# Yitran_IT900_Hutschiene_PIM7A_1_1.net
KiCad netlist of a schematic drawn in EAGLE
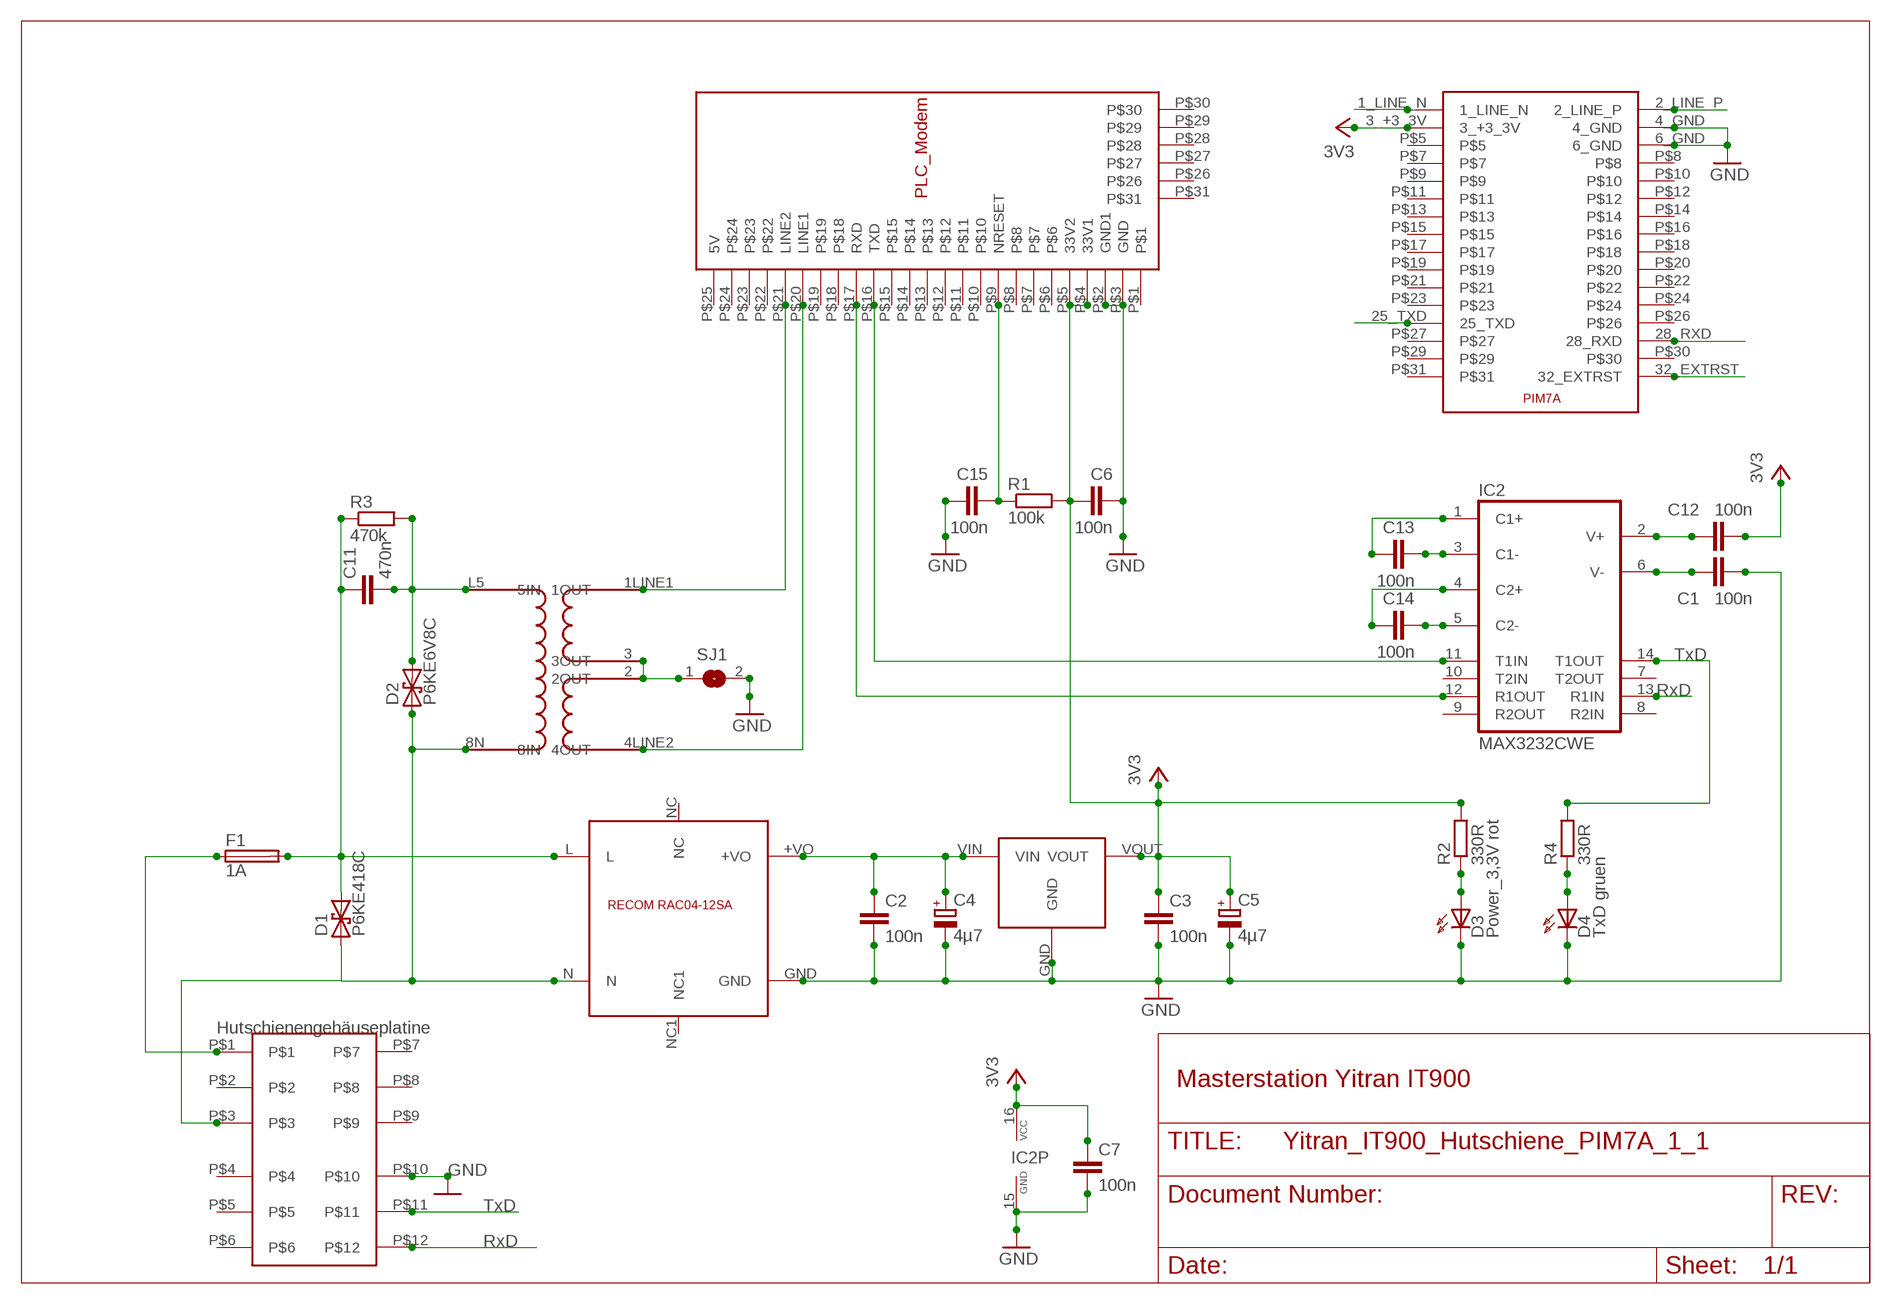
[diagram p0: schematic, sheet 1]

(export (version "E")
  (design (tool "Eeschema 10.0.6"))
  (components
    (comp (ref "C1")
      (value "100n")
      (footprint "eagle-import:C1206K")
      (libsource (lib "eagle-import") (part "C-EUC1206K"))
    )
    (comp (ref "C2")
      (value "100n")
      (footprint "eagle-import:C1206K")
      (libsource (lib "eagle-import") (part "C-EUC1206K"))
    )
    (comp (ref "C3")
      (value "100n")
      (footprint "eagle-import:C1206K")
      (libsource (lib "eagle-import") (part "C-EUC1206K"))
    )
    (comp (ref "C4")
      (value "4µ7")
      (footprint "eagle-import:E2,5-5")
      (libsource (lib "eagle-import") (part "CPOL-EUE2.5-5"))
    )
    (comp (ref "C5")
      (value "4µ7")
      (footprint "eagle-import:E2,5-5")
      (libsource (lib "eagle-import") (part "CPOL-EUE2.5-5"))
    )
    (comp (ref "C6")
      (value "100n")
      (footprint "eagle-import:C1206K")
      (libsource (lib "eagle-import") (part "C-EUC1206K"))
    )
    (comp (ref "C7")
      (value "100n")
      (footprint "eagle-import:C1206K")
      (libsource (lib "eagle-import") (part "C-EUC1206K"))
    )
    (comp (ref "C11")
      (value "470n")
      (footprint "eagle-import:C150-091X182")
      (libsource (lib "eagle-import") (part "C-EU150-091X182"))
    )
    (comp (ref "C12")
      (value "100n")
      (footprint "eagle-import:C1206K")
      (libsource (lib "eagle-import") (part "C-EUC1206K"))
    )
    (comp (ref "C13")
      (value "100n")
      (footprint "eagle-import:C1206K")
      (libsource (lib "eagle-import") (part "C-EUC1206K"))
    )
    (comp (ref "C14")
      (value "100n")
      (footprint "eagle-import:C1206K")
      (libsource (lib "eagle-import") (part "C-EUC1206K"))
    )
    (comp (ref "C15")
      (value "100n")
      (footprint "eagle-import:C1206K")
      (libsource (lib "eagle-import") (part "C-EUC1206K"))
    )
    (comp (ref "D1")
      (value "P6KE418C")
      (footprint "eagle-import:CB417-15")
      (libsource (lib "eagle-import") (part "P6KEXXC"))
    )
    (comp (ref "D2")
      (value "P6KE6V8C")
      (footprint "eagle-import:CB417-15")
      (libsource (lib "eagle-import") (part "P6KEXXC"))
    )
    (comp (ref "D3")
      (value "Power_3,3V rot")
      (footprint "eagle-import:HLMP6")
      (fields (field (name "MF") "AGILENT TECHNOLOGIES") (field (name "MPN") "HLMP-6500"))
      (libsource (lib "eagle-import") (part "HLMP6"))
    )
    (comp (ref "D4")
      (value "TxD gruen")
      (footprint "eagle-import:HLMP6")
      (fields (field (name "MF") "AGILENT TECHNOLOGIES") (field (name "MPN") "HLMP-6500"))
      (libsource (lib "eagle-import") (part "HLMP6"))
    )
    (comp (ref "F1")
      (value "1A")
      (footprint "eagle-import:TR5")
      (libsource (lib "eagle-import") (part "TR5"))
    )
    (comp (ref "IC2")
      (value "MAX3232CWE")
      (footprint "eagle-import:SO16L")
      (fields (field (name "MF") "MAXIM") (field (name "MPN") "MAX3232CWE+"))
      (libsource (lib "eagle-import") (part "MAX3232WEC"))
    )
    (comp (ref "R1")
      (value "100k")
      (footprint "eagle-import:M1406")
      (libsource (lib "eagle-import") (part "R-EU_M1406"))
    )
    (comp (ref "R2")
      (value "330R")
      (footprint "eagle-import:R1206")
      (libsource (lib "eagle-import") (part "R-EU_R1206"))
    )
    (comp (ref "R3")
      (value "470k")
      (footprint "eagle-import:0309_10")
      (libsource (lib "eagle-import") (part "R-EU_0309/10"))
    )
    (comp (ref "R4")
      (value "330R")
      (footprint "eagle-import:R1206")
      (libsource (lib "eagle-import") (part "R-EU_R1206"))
    )
    (comp (ref "SJ1")
      (value "SJW")
      (footprint "eagle-import:SJW")
      (libsource (lib "eagle-import") (part "SJW"))
    )
    (comp (ref "U$1")
      (value "RECOM_783_3")
      (footprint "eagle-import:RECOM785X")
      (libsource (lib "eagle-import") (part "RECOM_785_05"))
    )
    (comp (ref "U$2")
      (value "LDG-A-12")
      (footprint "eagle-import:LDG-A-12")
      (libsource (lib "eagle-import") (part "LDG-A-12"))
    )
    (comp (ref "U$3")
      (value "MODEMSTECKER")
      (footprint "eagle-import:MODEM_FUSS")
      (libsource (lib "eagle-import") (part "MODEMSTECKER"))
    )
    (comp (ref "U$4")
      (value "IT900PIM7A")
      (footprint "eagle-import:IT900PIM7A")
      (libsource (lib "eagle-import") (part "IT900PIM7A"))
    )
    (comp (ref "U$9")
      (value "RECOM_RAC04_12SA")
      (footprint "eagle-import:RAC04_12SA")
      (libsource (lib "eagle-import") (part "RECOM_RAC04_12SA"))
    )
    (comp (ref "U$10")
      (value "PLC_UEBERTRAGER_V2")
      (footprint "eagle-import:PLC-UEBERTRAGER_V2")
      (libsource (lib "eagle-import") (part "PLC_UEBERTRAGER_V2"))
    )
  )
  (nets
    (net (code "1") (name "/EXTRST") (class "Default")
      (node (ref "C15") (pin "2") (pinfunction "2_2") (pintype "passive"))
      (node (ref "R1") (pin "1") (pinfunction "1_1") (pintype "passive"))
      (node (ref "U$3") (pin "P$9") (pinfunction "NRESET_P$9") (pintype "bidirectional"))
      (node (ref "U$4") (pin "32_EXTRST") (pinfunction "32_EXTRST_32_EXTRST") (pintype "bidirectional"))
    )
    (net (code "2") (name "/LINE1") (class "Default")
      (node (ref "U$10") (pin "4LINE2") (pinfunction "4OUT_4LINE2") (pintype "output"))
      (node (ref "U$3") (pin "P$20") (pinfunction "LINE1_P$20") (pintype "bidirectional"))
      (node (ref "U$4") (pin "1_LINE_N") (pinfunction "1_LINE_N_1_LINE_N") (pintype "bidirectional"))
    )
    (net (code "3") (name "/LINE2") (class "Default")
      (node (ref "U$10") (pin "1LINE1") (pinfunction "1OUT_1LINE1") (pintype "output"))
      (node (ref "U$3") (pin "P$21") (pinfunction "LINE2_P$21") (pintype "bidirectional"))
      (node (ref "U$4") (pin "2_LINE_P") (pinfunction "2_LINE_P_2_LINE_P") (pintype "bidirectional"))
    )
    (net (code "4") (name "/RX") (class "Default")
      (node (ref "IC2") (pin "12") (pinfunction "R1OUT_12") (pintype "output"))
      (node (ref "U$3") (pin "P$17") (pinfunction "RXD_P$17") (pintype "bidirectional"))
      (node (ref "U$4") (pin "28_RXD") (pinfunction "28_RXD_28_RXD") (pintype "bidirectional"))
    )
    (net (code "5") (name "/RXD") (class "Default")
      (node (ref "IC2") (pin "13") (pinfunction "R1IN_13") (pintype "input"))
      (node (ref "U$2") (pin "P$12") (pinfunction "P$12_P$12") (pintype "bidirectional"))
    )
    (net (code "6") (name "/TX") (class "Default")
      (node (ref "IC2") (pin "11") (pinfunction "T1IN_11") (pintype "input"))
      (node (ref "U$3") (pin "P$16") (pinfunction "TXD_P$16") (pintype "bidirectional"))
      (node (ref "U$4") (pin "25_TXD") (pinfunction "25_TXD_25_TXD") (pintype "bidirectional"))
    )
    (net (code "7") (name "/TXD") (class "Default")
      (node (ref "IC2") (pin "14") (pinfunction "T1OUT_14") (pintype "output"))
      (node (ref "R4") (pin "2") (pinfunction "2_2") (pintype "passive"))
      (node (ref "U$2") (pin "P$11") (pinfunction "P$11_P$11") (pintype "bidirectional"))
    )
    (net (code "8") (name "3V3") (class "Default")
      (node (ref "C12") (pin "2") (pinfunction "2_2") (pintype "passive"))
      (node (ref "C3") (pin "1") (pinfunction "1_1") (pintype "passive"))
      (node (ref "C5") (pin "+") (pinfunction "+_+") (pintype "passive"))
      (node (ref "C6") (pin "1") (pinfunction "1_1") (pintype "passive"))
      (node (ref "C7") (pin "1") (pinfunction "1_1") (pintype "passive"))
      (node (ref "IC2") (pin "16") (pinfunction "VCC_16") (pintype "power_in"))
      (node (ref "R1") (pin "2") (pinfunction "2_2") (pintype "passive"))
      (node (ref "R2") (pin "2") (pinfunction "2_2") (pintype "passive"))
      (node (ref "U$1") (pin "VOUT") (pinfunction "VOUT_VOUT") (pintype "bidirectional"))
      (node (ref "U$3") (pin "P$4") (pinfunction "33V1_P$4") (pintype "bidirectional"))
      (node (ref "U$3") (pin "P$5") (pinfunction "33V2_P$5") (pintype "bidirectional"))
      (node (ref "U$4") (pin "3_+3_3V") (pinfunction "3_+3_3V_3_+3_3V") (pintype "bidirectional"))
    )
    (net (code "9") (name "GND") (class "Default")
      (node (ref "C1") (pin "2") (pinfunction "2_2") (pintype "passive"))
      (node (ref "C15") (pin "1") (pinfunction "1_1") (pintype "passive"))
      (node (ref "C2") (pin "2") (pinfunction "2_2") (pintype "passive"))
      (node (ref "C3") (pin "2") (pinfunction "2_2") (pintype "passive"))
      (node (ref "C4") (pin "-") (pinfunction "-_-") (pintype "passive"))
      (node (ref "C5") (pin "-") (pinfunction "-_-") (pintype "passive"))
      (node (ref "C6") (pin "2") (pinfunction "2_2") (pintype "passive"))
      (node (ref "C7") (pin "2") (pinfunction "2_2") (pintype "passive"))
      (node (ref "D3") (pin "K") (pinfunction "K_K") (pintype "passive"))
      (node (ref "D4") (pin "K") (pinfunction "K_K") (pintype "passive"))
      (node (ref "IC2") (pin "15") (pinfunction "GND_15") (pintype "power_in"))
      (node (ref "SJ1") (pin "2") (pinfunction "2_2") (pintype "passive"))
      (node (ref "U$1") (pin "GND") (pinfunction "GND_GND") (pintype "bidirectional"))
      (node (ref "U$2") (pin "P$10") (pinfunction "P$10_P$10") (pintype "bidirectional"))
      (node (ref "U$3") (pin "P$2") (pinfunction "GND1_P$2") (pintype "bidirectional"))
      (node (ref "U$3") (pin "P$3") (pinfunction "GND_P$3") (pintype "bidirectional"))
      (node (ref "U$4") (pin "4_GND") (pinfunction "4_GND_4_GND") (pintype "bidirectional"))
      (node (ref "U$4") (pin "6_GND") (pinfunction "6_GND_6_GND") (pintype "bidirectional"))
      (node (ref "U$9") (pin "GND") (pinfunction "GND_GND") (pintype "bidirectional"))
    )
    (net (code "10") (name "Net-(C2-Pad1)") (class "Default")
      (node (ref "C2") (pin "1") (pinfunction "1_1") (pintype "passive"))
      (node (ref "C4") (pin "+") (pinfunction "+_+") (pintype "passive"))
      (node (ref "U$1") (pin "VIN") (pinfunction "VIN_VIN") (pintype "bidirectional"))
      (node (ref "U$9") (pin "+VO") (pinfunction "+VO_+VO") (pintype "bidirectional"))
    )
    (net (code "11") (name "Net-(D1-1)") (class "Default")
      (node (ref "D1") (pin "A") (pinfunction "1_A") (pintype "passive"))
      (node (ref "D2") (pin "A") (pinfunction "1_A") (pintype "passive"))
      (node (ref "U$10") (pin "8N") (pinfunction "8IN_8N") (pintype "input"))
      (node (ref "U$2") (pin "P$3") (pinfunction "P$3_P$3") (pintype "bidirectional"))
      (node (ref "U$9") (pin "N") (pinfunction "N_N") (pintype "bidirectional"))
    )
    (net (code "12") (name "Net-(D1-2)") (class "Default")
      (node (ref "C11") (pin "1") (pinfunction "1_1") (pintype "passive"))
      (node (ref "D1") (pin "C") (pinfunction "2_C") (pintype "passive"))
      (node (ref "F1") (pin "2") (pinfunction "2_2") (pintype "passive"))
      (node (ref "R3") (pin "1") (pinfunction "1_1") (pintype "passive"))
      (node (ref "U$9") (pin "L") (pinfunction "L_L") (pintype "bidirectional"))
    )
    (net (code "13") (name "Net-(D2-2)") (class "Default")
      (node (ref "C11") (pin "2") (pinfunction "2_2") (pintype "passive"))
      (node (ref "D2") (pin "C") (pinfunction "2_C") (pintype "passive"))
      (node (ref "R3") (pin "2") (pinfunction "2_2") (pintype "passive"))
      (node (ref "U$10") (pin "L5") (pinfunction "5IN_L5") (pintype "input"))
    )
    (net (code "14") (name "Net-(D3-PadA)") (class "Default")
      (node (ref "D3") (pin "A") (pinfunction "A_A") (pintype "passive"))
      (node (ref "R2") (pin "1") (pinfunction "1_1") (pintype "passive"))
    )
    (net (code "15") (name "Net-(D4-PadA)") (class "Default")
      (node (ref "D4") (pin "A") (pinfunction "A_A") (pintype "passive"))
      (node (ref "R4") (pin "1") (pinfunction "1_1") (pintype "passive"))
    )
    (net (code "16") (name "Net-(F1-Pad1)") (class "Default")
      (node (ref "F1") (pin "1") (pinfunction "1_1") (pintype "passive"))
      (node (ref "U$2") (pin "P$1") (pinfunction "P$1_P$1") (pintype "bidirectional"))
    )
    (net (code "17") (name "Net-(IC2A-C1+)") (class "Default")
      (node (ref "C13") (pin "1") (pinfunction "1_1") (pintype "passive"))
      (node (ref "IC2") (pin "1") (pinfunction "C1+_1") (pintype "bidirectional"))
    )
    (net (code "18") (name "Net-(IC2A-C1-)") (class "Default")
      (node (ref "C13") (pin "2") (pinfunction "2_2") (pintype "passive"))
      (node (ref "IC2") (pin "3") (pinfunction "C1-_3") (pintype "bidirectional"))
    )
    (net (code "19") (name "Net-(IC2A-C2+)") (class "Default")
      (node (ref "C14") (pin "1") (pinfunction "1_1") (pintype "passive"))
      (node (ref "IC2") (pin "4") (pinfunction "C2+_4") (pintype "bidirectional"))
    )
    (net (code "20") (name "Net-(IC2A-C2-)") (class "Default")
      (node (ref "C14") (pin "2") (pinfunction "2_2") (pintype "passive"))
      (node (ref "IC2") (pin "5") (pinfunction "C2-_5") (pintype "bidirectional"))
    )
    (net (code "21") (name "Net-(IC2A-V+)") (class "Default")
      (node (ref "C12") (pin "1") (pinfunction "1_1") (pintype "passive"))
      (node (ref "IC2") (pin "2") (pinfunction "V+_2") (pintype "bidirectional"))
    )
    (net (code "22") (name "Net-(IC2A-V-)") (class "Default")
      (node (ref "C1") (pin "1") (pinfunction "1_1") (pintype "passive"))
      (node (ref "IC2") (pin "6") (pinfunction "V-_6") (pintype "bidirectional"))
    )
    (net (code "23") (name "Net-(U$10-2OUT)") (class "Default")
      (node (ref "SJ1") (pin "1") (pinfunction "1_1") (pintype "passive"))
      (node (ref "U$10") (pin "2") (pinfunction "2OUT_2") (pintype "output"))
      (node (ref "U$10") (pin "3") (pinfunction "3OUT_3") (pintype "output"))
    )
    (net (code "24") (name "unconnected-(IC2A-R2IN-Pad8)") (class "Default")
      (node (ref "IC2") (pin "8") (pinfunction "R2IN_8") (pintype "input"))
    )
    (net (code "25") (name "unconnected-(IC2A-R2OUT-Pad9)") (class "Default")
      (node (ref "IC2") (pin "9") (pinfunction "R2OUT_9") (pintype "output"))
    )
    (net (code "26") (name "unconnected-(IC2A-T2IN-Pad10)") (class "Default")
      (node (ref "IC2") (pin "10") (pinfunction "T2IN_10") (pintype "input"))
    )
    (net (code "27") (name "unconnected-(IC2A-T2OUT-Pad7)") (class "Default")
      (node (ref "IC2") (pin "7") (pinfunction "T2OUT_7") (pintype "output"))
    )
    (net (code "28") (name "unconnected-(U$2-PadP$2)") (class "Default")
      (node (ref "U$2") (pin "P$2") (pinfunction "P$2_P$2") (pintype "bidirectional"))
    )
    (net (code "29") (name "unconnected-(U$2-PadP$4)") (class "Default")
      (node (ref "U$2") (pin "P$4") (pinfunction "P$4_P$4") (pintype "bidirectional"))
    )
    (net (code "30") (name "unconnected-(U$2-PadP$5)") (class "Default")
      (node (ref "U$2") (pin "P$5") (pinfunction "P$5_P$5") (pintype "bidirectional"))
    )
    (net (code "31") (name "unconnected-(U$2-PadP$6)") (class "Default")
      (node (ref "U$2") (pin "P$6") (pinfunction "P$6_P$6") (pintype "bidirectional"))
    )
    (net (code "32") (name "unconnected-(U$2-PadP$7)") (class "Default")
      (node (ref "U$2") (pin "P$7") (pinfunction "P$7_P$7") (pintype "bidirectional"))
    )
    (net (code "33") (name "unconnected-(U$2-PadP$8)") (class "Default")
      (node (ref "U$2") (pin "P$8") (pinfunction "P$8_P$8") (pintype "bidirectional"))
    )
    (net (code "34") (name "unconnected-(U$2-PadP$9)") (class "Default")
      (node (ref "U$2") (pin "P$9") (pinfunction "P$9_P$9") (pintype "bidirectional"))
    )
    (net (code "35") (name "unconnected-(U$3-5V-PadP$25)") (class "Default")
      (node (ref "U$3") (pin "P$25") (pinfunction "5V_P$25") (pintype "bidirectional"))
    )
    (net (code "36") (name "unconnected-(U$3-PadP$1)") (class "Default")
      (node (ref "U$3") (pin "P$1") (pinfunction "P$1_P$1") (pintype "bidirectional"))
    )
    (net (code "37") (name "unconnected-(U$3-PadP$6)") (class "Default")
      (node (ref "U$3") (pin "P$6") (pinfunction "P$6_P$6") (pintype "bidirectional"))
    )
    (net (code "38") (name "unconnected-(U$3-PadP$7)") (class "Default")
      (node (ref "U$3") (pin "P$7") (pinfunction "P$7_P$7") (pintype "bidirectional"))
    )
    (net (code "39") (name "unconnected-(U$3-PadP$8)") (class "Default")
      (node (ref "U$3") (pin "P$8") (pinfunction "P$8_P$8") (pintype "bidirectional"))
    )
    (net (code "40") (name "unconnected-(U$3-PadP$10)") (class "Default")
      (node (ref "U$3") (pin "P$10") (pinfunction "P$10_P$10") (pintype "bidirectional"))
    )
    (net (code "41") (name "unconnected-(U$3-PadP$11)") (class "Default")
      (node (ref "U$3") (pin "P$11") (pinfunction "P$11_P$11") (pintype "bidirectional"))
    )
    (net (code "42") (name "unconnected-(U$3-PadP$12)") (class "Default")
      (node (ref "U$3") (pin "P$12") (pinfunction "P$12_P$12") (pintype "bidirectional"))
    )
    (net (code "43") (name "unconnected-(U$3-PadP$13)") (class "Default")
      (node (ref "U$3") (pin "P$13") (pinfunction "P$13_P$13") (pintype "bidirectional"))
    )
    (net (code "44") (name "unconnected-(U$3-PadP$14)") (class "Default")
      (node (ref "U$3") (pin "P$14") (pinfunction "P$14_P$14") (pintype "bidirectional"))
    )
    (net (code "45") (name "unconnected-(U$3-PadP$15)") (class "Default")
      (node (ref "U$3") (pin "P$15") (pinfunction "P$15_P$15") (pintype "bidirectional"))
    )
    (net (code "46") (name "unconnected-(U$3-PadP$18)") (class "Default")
      (node (ref "U$3") (pin "P$18") (pinfunction "P$18_P$18") (pintype "bidirectional"))
    )
    (net (code "47") (name "unconnected-(U$3-PadP$19)") (class "Default")
      (node (ref "U$3") (pin "P$19") (pinfunction "P$19_P$19") (pintype "bidirectional"))
    )
    (net (code "48") (name "unconnected-(U$3-PadP$22)") (class "Default")
      (node (ref "U$3") (pin "P$22") (pinfunction "P$22_P$22") (pintype "bidirectional"))
    )
    (net (code "49") (name "unconnected-(U$3-PadP$23)") (class "Default")
      (node (ref "U$3") (pin "P$23") (pinfunction "P$23_P$23") (pintype "bidirectional"))
    )
    (net (code "50") (name "unconnected-(U$3-PadP$24)") (class "Default")
      (node (ref "U$3") (pin "P$24") (pinfunction "P$24_P$24") (pintype "bidirectional"))
    )
    (net (code "51") (name "unconnected-(U$3-PadP$26)") (class "Default")
      (node (ref "U$3") (pin "P$26") (pinfunction "P$26_P$26") (pintype "bidirectional"))
    )
    (net (code "52") (name "unconnected-(U$3-PadP$27)") (class "Default")
      (node (ref "U$3") (pin "P$27") (pinfunction "P$27_P$27") (pintype "bidirectional"))
    )
    (net (code "53") (name "unconnected-(U$3-PadP$28)") (class "Default")
      (node (ref "U$3") (pin "P$28") (pinfunction "P$28_P$28") (pintype "bidirectional"))
    )
    (net (code "54") (name "unconnected-(U$3-PadP$29)") (class "Default")
      (node (ref "U$3") (pin "P$29") (pinfunction "P$29_P$29") (pintype "bidirectional"))
    )
    (net (code "55") (name "unconnected-(U$3-PadP$30)") (class "Default")
      (node (ref "U$3") (pin "P$30") (pinfunction "P$30_P$30") (pintype "bidirectional"))
    )
    (net (code "56") (name "unconnected-(U$3-PadP$31)") (class "Default")
      (node (ref "U$3") (pin "P$31") (pinfunction "P$31_P$31") (pintype "bidirectional"))
    )
    (net (code "57") (name "unconnected-(U$4-PadP$5)") (class "Default")
      (node (ref "U$4") (pin "P$5") (pinfunction "P$5_P$5") (pintype "bidirectional"))
    )
    (net (code "58") (name "unconnected-(U$4-PadP$7)") (class "Default")
      (node (ref "U$4") (pin "P$7") (pinfunction "P$7_P$7") (pintype "bidirectional"))
    )
    (net (code "59") (name "unconnected-(U$4-PadP$8)") (class "Default")
      (node (ref "U$4") (pin "P$8") (pinfunction "P$8_P$8") (pintype "bidirectional"))
    )
    (net (code "60") (name "unconnected-(U$4-PadP$9)") (class "Default")
      (node (ref "U$4") (pin "P$9") (pinfunction "P$9_P$9") (pintype "bidirectional"))
    )
    (net (code "61") (name "unconnected-(U$4-PadP$10)") (class "Default")
      (node (ref "U$4") (pin "P$10") (pinfunction "P$10_P$10") (pintype "bidirectional"))
    )
    (net (code "62") (name "unconnected-(U$4-PadP$11)") (class "Default")
      (node (ref "U$4") (pin "P$11") (pinfunction "P$11_P$11") (pintype "bidirectional"))
    )
    (net (code "63") (name "unconnected-(U$4-PadP$12)") (class "Default")
      (node (ref "U$4") (pin "P$12") (pinfunction "P$12_P$12") (pintype "bidirectional"))
    )
    (net (code "64") (name "unconnected-(U$4-PadP$13)") (class "Default")
      (node (ref "U$4") (pin "P$13") (pinfunction "P$13_P$13") (pintype "bidirectional"))
    )
    (net (code "65") (name "unconnected-(U$4-PadP$14)") (class "Default")
      (node (ref "U$4") (pin "P$14") (pinfunction "P$14_P$14") (pintype "bidirectional"))
    )
    (net (code "66") (name "unconnected-(U$4-PadP$15)") (class "Default")
      (node (ref "U$4") (pin "P$15") (pinfunction "P$15_P$15") (pintype "bidirectional"))
    )
    (net (code "67") (name "unconnected-(U$4-PadP$16)") (class "Default")
      (node (ref "U$4") (pin "P$16") (pinfunction "P$16_P$16") (pintype "bidirectional"))
    )
    (net (code "68") (name "unconnected-(U$4-PadP$17)") (class "Default")
      (node (ref "U$4") (pin "P$17") (pinfunction "P$17_P$17") (pintype "bidirectional"))
    )
    (net (code "69") (name "unconnected-(U$4-PadP$18)") (class "Default")
      (node (ref "U$4") (pin "P$18") (pinfunction "P$18_P$18") (pintype "bidirectional"))
    )
    (net (code "70") (name "unconnected-(U$4-PadP$19)") (class "Default")
      (node (ref "U$4") (pin "P$19") (pinfunction "P$19_P$19") (pintype "bidirectional"))
    )
    (net (code "71") (name "unconnected-(U$4-PadP$20)") (class "Default")
      (node (ref "U$4") (pin "P$20") (pinfunction "P$20_P$20") (pintype "bidirectional"))
    )
    (net (code "72") (name "unconnected-(U$4-PadP$21)") (class "Default")
      (node (ref "U$4") (pin "P$21") (pinfunction "P$21_P$21") (pintype "bidirectional"))
    )
    (net (code "73") (name "unconnected-(U$4-PadP$22)") (class "Default")
      (node (ref "U$4") (pin "P$22") (pinfunction "P$22_P$22") (pintype "bidirectional"))
    )
    (net (code "74") (name "unconnected-(U$4-PadP$23)") (class "Default")
      (node (ref "U$4") (pin "P$23") (pinfunction "P$23_P$23") (pintype "bidirectional"))
    )
    (net (code "75") (name "unconnected-(U$4-PadP$24)") (class "Default")
      (node (ref "U$4") (pin "P$24") (pinfunction "P$24_P$24") (pintype "bidirectional"))
    )
    (net (code "76") (name "unconnected-(U$4-PadP$26)") (class "Default")
      (node (ref "U$4") (pin "P$26") (pinfunction "P$26_P$26") (pintype "bidirectional"))
    )
    (net (code "77") (name "unconnected-(U$4-PadP$27)") (class "Default")
      (node (ref "U$4") (pin "P$27") (pinfunction "P$27_P$27") (pintype "bidirectional"))
    )
    (net (code "78") (name "unconnected-(U$4-PadP$29)") (class "Default")
      (node (ref "U$4") (pin "P$29") (pinfunction "P$29_P$29") (pintype "bidirectional"))
    )
    (net (code "79") (name "unconnected-(U$4-PadP$30)") (class "Default")
      (node (ref "U$4") (pin "P$30") (pinfunction "P$30_P$30") (pintype "bidirectional"))
    )
    (net (code "80") (name "unconnected-(U$4-PadP$31)") (class "Default")
      (node (ref "U$4") (pin "P$31") (pinfunction "P$31_P$31") (pintype "bidirectional"))
    )
    (net (code "81") (name "unconnected-(U$9-PadNC)") (class "Default")
      (node (ref "U$9") (pin "NC") (pinfunction "NC_NC") (pintype "bidirectional"))
    )
    (net (code "82") (name "unconnected-(U$9-PadNC1)") (class "Default")
      (node (ref "U$9") (pin "NC1") (pinfunction "NC1_NC1") (pintype "bidirectional"))
    )
  )
)
